# rapidshark-main-breakout-top-mk-1_D.net
KiCad netlist of a schematic drawn in EAGLE
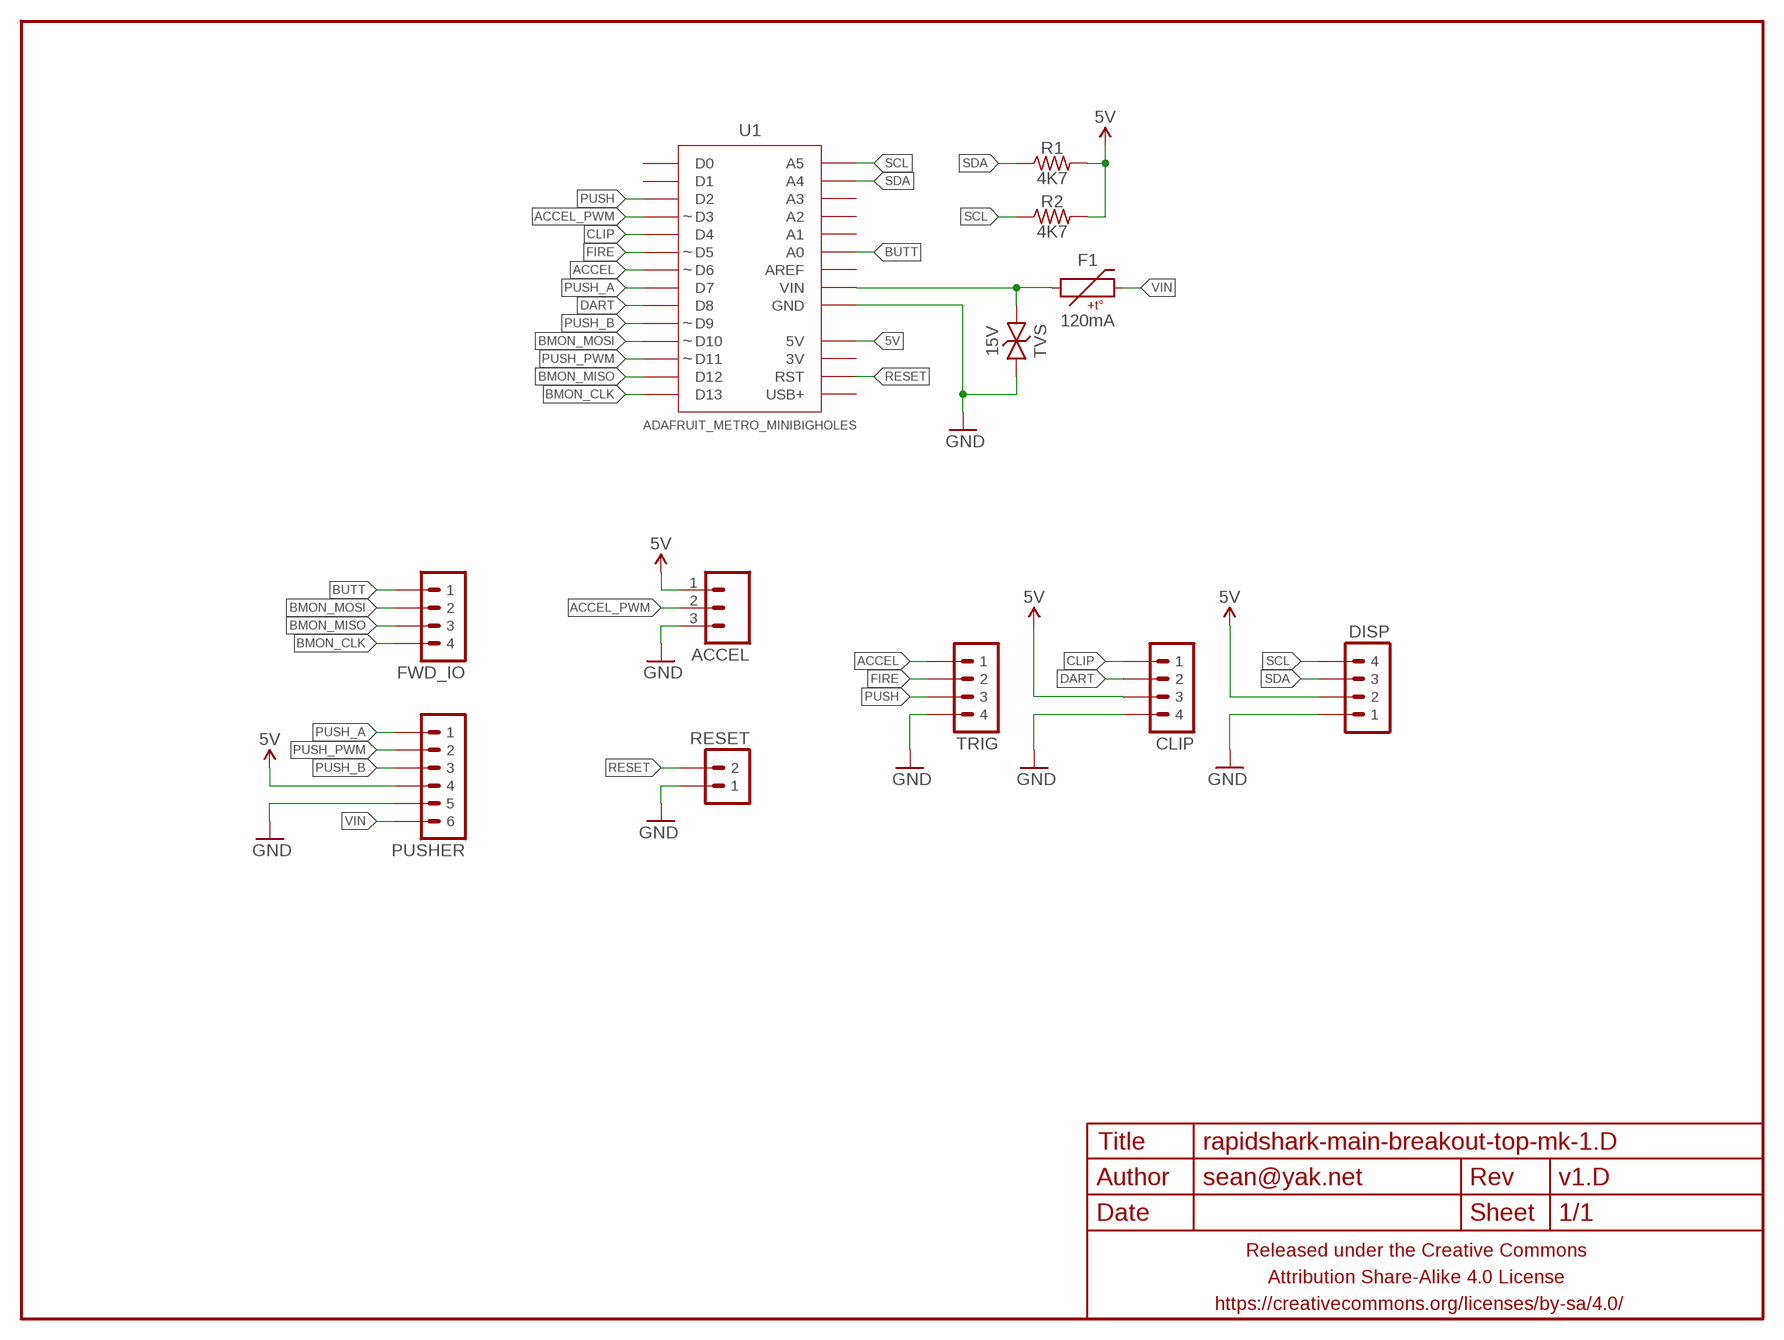
[diagram p0: schematic, sheet 1]

(export (version "E")
  (design (tool "Eeschema 10.0.6"))
  (components
    (comp (ref "ACCEL")
      (value "M03JST-PTH-VERT-CENTERED")
      (footprint "eagle-import:JST-3-PH-VERT-PTH-CENTERED")
      (libsource (lib "eagle-import") (part "M03JST-PTH-VERT-CENTERED"))
    )
    (comp (ref "CLIP")
      (value "M04JST-PTH-VERT")
      (footprint "eagle-import:JST-4-PH-VERT-PTH")
      (libsource (lib "eagle-import") (part "M04JST-PTH-VERT"))
    )
    (comp (ref "DISP")
      (value "M04JST-PTH-VERT")
      (footprint "eagle-import:JST-4-PH-VERT-PTH")
      (libsource (lib "eagle-import") (part "M04JST-PTH-VERT"))
    )
    (comp (ref "F1")
      (value "120mA")
      (footprint "eagle-import:PTC-1206")
      (libsource (lib "eagle-import") (part "PTCSMD"))
    )
    (comp (ref "FRAME1")
      (value "FRAME-LETTERNO_PACKAGE")
      (footprint "eagle-import:DUMMY")
      (fields (field (name "DESIGNER") "sean@yak.net") (field (name "VERSION") "v1.D"))
      (libsource (lib "eagle-import") (part "FRAME-LETTERNO_PACKAGE"))
    )
    (comp (ref "FWD_IO")
      (value "M04JST-PTH-VERT")
      (footprint "eagle-import:JST-4-PH-VERT-PTH")
      (libsource (lib "eagle-import") (part "M04JST-PTH-VERT"))
    )
    (comp (ref "PUSHER")
      (value "M06JST-PH-PTH-VERT")
      (footprint "eagle-import:JST-6-PH-VERT-PTH")
      (libsource (lib "eagle-import") (part "M06JST-PH-PTH-VERT"))
    )
    (comp (ref "R1")
      (value "4K7")
      (footprint "eagle-import:R0603-TIGHTER")
      (libsource (lib "eagle-import") (part "RESISTORR0603-TIGHTER"))
    )
    (comp (ref "R2")
      (value "4K7")
      (footprint "eagle-import:R0603-TIGHTER")
      (libsource (lib "eagle-import") (part "RESISTORR0603-TIGHTER"))
    )
    (comp (ref "RESET")
      (value "M02JST-PTH-VERT")
      (footprint "eagle-import:JST-2-PH-VERT-PTH")
      (libsource (lib "eagle-import") (part "M02JST-PTH-VERT"))
    )
    (comp (ref "TRIG")
      (value "M04JST-PTH-VERT")
      (footprint "eagle-import:JST-4-PH-VERT-PTH")
      (libsource (lib "eagle-import") (part "M04JST-PTH-VERT"))
    )
    (comp (ref "TVS")
      (value "15V")
      (footprint "eagle-import:SMA-DIODE-TVS-BIDIR")
      (libsource (lib "eagle-import") (part "TVSSMA"))
    )
    (comp (ref "U1")
      (value "ADAFRUIT_METRO_MINIBIGHOLES")
      (footprint "eagle-import:ADAFRUIT_METRO_MINI_BIGHOLES")
      (libsource (lib "eagle-import") (part "ADAFRUIT_METRO_MINIBIGHOLES"))
    )
  )
  (nets
    (net (code "1") (name "5V") (class "Default")
      (node (ref "ACCEL") (pin "1") (pinfunction "1_1") (pintype "passive"))
      (node (ref "CLIP") (pin "3") (pinfunction "3_3") (pintype "passive"))
      (node (ref "DISP") (pin "2") (pinfunction "2_2") (pintype "passive"))
      (node (ref "PUSHER") (pin "4") (pinfunction "4_4") (pintype "passive"))
      (node (ref "R1") (pin "2") (pinfunction "2_2") (pintype "passive"))
      (node (ref "R2") (pin "2") (pinfunction "2_2") (pintype "passive"))
      (node (ref "U1") (pin "18") (pinfunction "5V_18") (pintype "bidirectional"))
    )
    (net (code "2") (name "ACCEL") (class "Default")
      (node (ref "TRIG") (pin "1") (pinfunction "1_1") (pintype "passive"))
      (node (ref "U1") (pin "7") (pinfunction "D6_7") (pintype "bidirectional"))
    )
    (net (code "3") (name "ACCEL_PWM") (class "Default")
      (node (ref "ACCEL") (pin "2") (pinfunction "2_2") (pintype "passive"))
      (node (ref "U1") (pin "4") (pinfunction "D3_4") (pintype "bidirectional"))
    )
    (net (code "4") (name "BMON_CLK") (class "Default")
      (node (ref "FWD_IO") (pin "4") (pinfunction "4_4") (pintype "passive"))
      (node (ref "U1") (pin "14") (pinfunction "D13_14") (pintype "bidirectional"))
    )
    (net (code "5") (name "BMON_MISO") (class "Default")
      (node (ref "FWD_IO") (pin "3") (pinfunction "3_3") (pintype "passive"))
      (node (ref "U1") (pin "13") (pinfunction "D12_13") (pintype "bidirectional"))
    )
    (net (code "6") (name "BMON_MOSI") (class "Default")
      (node (ref "FWD_IO") (pin "2") (pinfunction "2_2") (pintype "passive"))
      (node (ref "U1") (pin "11") (pinfunction "D10_11") (pintype "bidirectional"))
    )
    (net (code "7") (name "BUTT") (class "Default")
      (node (ref "FWD_IO") (pin "1") (pinfunction "1_1") (pintype "passive"))
      (node (ref "U1") (pin "23") (pinfunction "A0_23") (pintype "bidirectional"))
    )
    (net (code "8") (name "CLIP") (class "Default")
      (node (ref "CLIP") (pin "1") (pinfunction "1_1") (pintype "passive"))
      (node (ref "U1") (pin "5") (pinfunction "D4_5") (pintype "bidirectional"))
    )
    (net (code "9") (name "DART") (class "Default")
      (node (ref "CLIP") (pin "2") (pinfunction "2_2") (pintype "passive"))
      (node (ref "U1") (pin "9") (pinfunction "D8_9") (pintype "bidirectional"))
    )
    (net (code "10") (name "FIRE") (class "Default")
      (node (ref "TRIG") (pin "2") (pinfunction "2_2") (pintype "passive"))
      (node (ref "U1") (pin "6") (pinfunction "D5_6") (pintype "bidirectional"))
    )
    (net (code "11") (name "GND") (class "Default")
      (node (ref "ACCEL") (pin "3") (pinfunction "3_3") (pintype "passive"))
      (node (ref "CLIP") (pin "4") (pinfunction "4_4") (pintype "passive"))
      (node (ref "DISP") (pin "1") (pinfunction "1_1") (pintype "passive"))
      (node (ref "PUSHER") (pin "5") (pinfunction "5_5") (pintype "passive"))
      (node (ref "RESET") (pin "1") (pinfunction "1_1") (pintype "passive"))
      (node (ref "TRIG") (pin "4") (pinfunction "4_4") (pintype "passive"))
      (node (ref "TVS") (pin "1") (pinfunction "1_1") (pintype "passive"))
      (node (ref "U1") (pin "19") (pinfunction "GND_19") (pintype "bidirectional"))
      (node (ref "U1") (pin "20") (pinfunction "GND_20") (pintype "bidirectional"))
    )
    (net (code "12") (name "Net-(U1-VIN)") (class "Default")
      (node (ref "F1") (pin "1") (pinfunction "1_1") (pintype "passive"))
      (node (ref "TVS") (pin "2") (pinfunction "2_2") (pintype "passive"))
      (node (ref "U1") (pin "21") (pinfunction "VIN_21") (pintype "bidirectional"))
    )
    (net (code "13") (name "PUSH") (class "Default")
      (node (ref "TRIG") (pin "3") (pinfunction "3_3") (pintype "passive"))
      (node (ref "U1") (pin "3") (pinfunction "D2_3") (pintype "bidirectional"))
    )
    (net (code "14") (name "PUSH_A") (class "Default")
      (node (ref "PUSHER") (pin "1") (pinfunction "1_1") (pintype "passive"))
      (node (ref "U1") (pin "8") (pinfunction "D7_8") (pintype "bidirectional"))
    )
    (net (code "15") (name "PUSH_B") (class "Default")
      (node (ref "PUSHER") (pin "3") (pinfunction "3_3") (pintype "passive"))
      (node (ref "U1") (pin "10") (pinfunction "D9_10") (pintype "bidirectional"))
    )
    (net (code "16") (name "PUSH_PWM") (class "Default")
      (node (ref "PUSHER") (pin "2") (pinfunction "2_2") (pintype "passive"))
      (node (ref "U1") (pin "12") (pinfunction "D11_12") (pintype "bidirectional"))
    )
    (net (code "17") (name "RESET") (class "Default")
      (node (ref "RESET") (pin "2") (pinfunction "2_2") (pintype "passive"))
      (node (ref "U1") (pin "16") (pinfunction "RST_16") (pintype "bidirectional"))
    )
    (net (code "18") (name "SCL") (class "Default")
      (node (ref "DISP") (pin "4") (pinfunction "4_4") (pintype "passive"))
      (node (ref "R2") (pin "1") (pinfunction "1_1") (pintype "passive"))
      (node (ref "U1") (pin "28") (pinfunction "A5_28") (pintype "bidirectional"))
    )
    (net (code "19") (name "SDA") (class "Default")
      (node (ref "DISP") (pin "3") (pinfunction "3_3") (pintype "passive"))
      (node (ref "R1") (pin "1") (pinfunction "1_1") (pintype "passive"))
      (node (ref "U1") (pin "27") (pinfunction "A4_27") (pintype "bidirectional"))
    )
    (net (code "20") (name "VIN") (class "Default")
      (node (ref "F1") (pin "2") (pinfunction "2_2") (pintype "passive"))
      (node (ref "PUSHER") (pin "6") (pinfunction "6_6") (pintype "passive"))
    )
    (net (code "21") (name "unconnected-(U1-3V-Pad17)") (class "Default")
      (node (ref "U1") (pin "17") (pinfunction "3V_17") (pintype "bidirectional"))
    )
    (net (code "22") (name "unconnected-(U1-A1-Pad24)") (class "Default")
      (node (ref "U1") (pin "24") (pinfunction "A1_24") (pintype "bidirectional"))
    )
    (net (code "23") (name "unconnected-(U1-A2-Pad25)") (class "Default")
      (node (ref "U1") (pin "25") (pinfunction "A2_25") (pintype "bidirectional"))
    )
    (net (code "24") (name "unconnected-(U1-A3-Pad26)") (class "Default")
      (node (ref "U1") (pin "26") (pinfunction "A3_26") (pintype "bidirectional"))
    )
    (net (code "25") (name "unconnected-(U1-AREF-Pad22)") (class "Default")
      (node (ref "U1") (pin "22") (pinfunction "AREF_22") (pintype "bidirectional"))
    )
    (net (code "26") (name "unconnected-(U1-D0-Pad1)") (class "Default")
      (node (ref "U1") (pin "1") (pinfunction "D0_1") (pintype "bidirectional"))
    )
    (net (code "27") (name "unconnected-(U1-D1-Pad2)") (class "Default")
      (node (ref "U1") (pin "2") (pinfunction "D1_2") (pintype "bidirectional"))
    )
    (net (code "28") (name "unconnected-(U1-USB+-Pad15)") (class "Default")
      (node (ref "U1") (pin "15") (pinfunction "USB+_15") (pintype "bidirectional"))
    )
  )
)
